# EIB_A79024-001.net
KiCad netlist of a schematic drawn in EAGLE
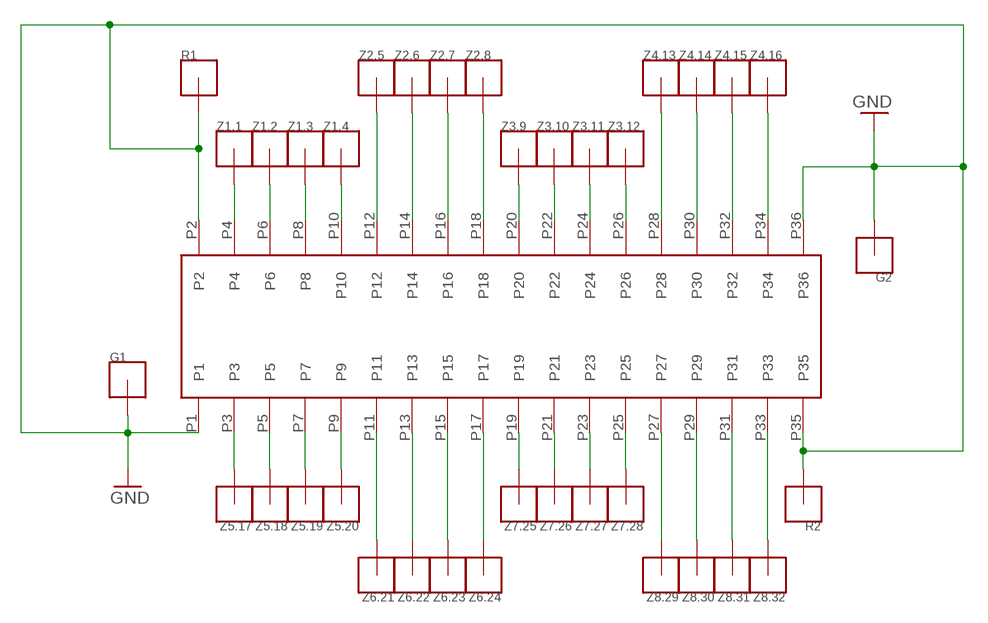
[diagram p0: schematic, sheet 1]

(export (version "E")
  (design (tool "Eeschema 10.0.6"))
  (components
    (comp (ref "A79024")
      (value "OMNETICS")
      (footprint "eagle-import:A79024")
      (libsource (lib "eagle-import") (part "OMNETICS"))
    )
    (comp (ref "G1")
      (value "S_P_HOLE")
      (footprint "eagle-import:S_P_HOLE")
      (libsource (lib "eagle-import") (part "S_P_HOLE"))
    )
    (comp (ref "G2")
      (value "S_P_HOLE")
      (footprint "eagle-import:S_P_HOLE")
      (libsource (lib "eagle-import") (part "S_P_HOLE"))
    )
    (comp (ref "R1")
      (value "S_P_HOLE")
      (footprint "eagle-import:S_P_HOLE")
      (libsource (lib "eagle-import") (part "S_P_HOLE"))
    )
    (comp (ref "R2")
      (value "S_P_HOLE")
      (footprint "eagle-import:S_P_HOLE")
      (libsource (lib "eagle-import") (part "S_P_HOLE"))
    )
    (comp (ref "Z1.1")
      (value "S_P_HOLE")
      (footprint "eagle-import:S_P_HOLE")
      (libsource (lib "eagle-import") (part "S_P_HOLE"))
    )
    (comp (ref "Z1.2")
      (value "S_P_HOLE")
      (footprint "eagle-import:S_P_HOLE")
      (libsource (lib "eagle-import") (part "S_P_HOLE"))
    )
    (comp (ref "Z1.3")
      (value "S_P_HOLE")
      (footprint "eagle-import:S_P_HOLE")
      (libsource (lib "eagle-import") (part "S_P_HOLE"))
    )
    (comp (ref "Z1.4")
      (value "S_P_HOLE")
      (footprint "eagle-import:S_P_HOLE")
      (libsource (lib "eagle-import") (part "S_P_HOLE"))
    )
    (comp (ref "Z2.5")
      (value "S_P_HOLE")
      (footprint "eagle-import:S_P_HOLE")
      (libsource (lib "eagle-import") (part "S_P_HOLE"))
    )
    (comp (ref "Z2.6")
      (value "S_P_HOLE")
      (footprint "eagle-import:S_P_HOLE")
      (libsource (lib "eagle-import") (part "S_P_HOLE"))
    )
    (comp (ref "Z2.7")
      (value "S_P_HOLE")
      (footprint "eagle-import:S_P_HOLE")
      (libsource (lib "eagle-import") (part "S_P_HOLE"))
    )
    (comp (ref "Z2.8")
      (value "S_P_HOLE")
      (footprint "eagle-import:S_P_HOLE")
      (libsource (lib "eagle-import") (part "S_P_HOLE"))
    )
    (comp (ref "Z3.9")
      (value "S_P_HOLE")
      (footprint "eagle-import:S_P_HOLE")
      (libsource (lib "eagle-import") (part "S_P_HOLE"))
    )
    (comp (ref "Z3.10")
      (value "S_P_HOLE")
      (footprint "eagle-import:S_P_HOLE")
      (libsource (lib "eagle-import") (part "S_P_HOLE"))
    )
    (comp (ref "Z3.11")
      (value "S_P_HOLE")
      (footprint "eagle-import:S_P_HOLE")
      (libsource (lib "eagle-import") (part "S_P_HOLE"))
    )
    (comp (ref "Z3.12")
      (value "S_P_HOLE")
      (footprint "eagle-import:S_P_HOLE")
      (libsource (lib "eagle-import") (part "S_P_HOLE"))
    )
    (comp (ref "Z4.13")
      (value "S_P_HOLE")
      (footprint "eagle-import:S_P_HOLE")
      (libsource (lib "eagle-import") (part "S_P_HOLE"))
    )
    (comp (ref "Z4.14")
      (value "S_P_HOLE")
      (footprint "eagle-import:S_P_HOLE")
      (libsource (lib "eagle-import") (part "S_P_HOLE"))
    )
    (comp (ref "Z4.15")
      (value "S_P_HOLE")
      (footprint "eagle-import:S_P_HOLE")
      (libsource (lib "eagle-import") (part "S_P_HOLE"))
    )
    (comp (ref "Z4.16")
      (value "S_P_HOLE")
      (footprint "eagle-import:S_P_HOLE")
      (libsource (lib "eagle-import") (part "S_P_HOLE"))
    )
    (comp (ref "Z5.17")
      (value "S_P_HOLE")
      (footprint "eagle-import:S_P_HOLE")
      (libsource (lib "eagle-import") (part "S_P_HOLE"))
    )
    (comp (ref "Z5.18")
      (value "S_P_HOLE")
      (footprint "eagle-import:S_P_HOLE")
      (libsource (lib "eagle-import") (part "S_P_HOLE"))
    )
    (comp (ref "Z5.19")
      (value "S_P_HOLE")
      (footprint "eagle-import:S_P_HOLE")
      (libsource (lib "eagle-import") (part "S_P_HOLE"))
    )
    (comp (ref "Z5.20")
      (value "S_P_HOLE")
      (footprint "eagle-import:S_P_HOLE")
      (libsource (lib "eagle-import") (part "S_P_HOLE"))
    )
    (comp (ref "Z6.21")
      (value "S_P_HOLE")
      (footprint "eagle-import:S_P_HOLE")
      (libsource (lib "eagle-import") (part "S_P_HOLE"))
    )
    (comp (ref "Z6.22")
      (value "S_P_HOLE")
      (footprint "eagle-import:S_P_HOLE")
      (libsource (lib "eagle-import") (part "S_P_HOLE"))
    )
    (comp (ref "Z6.23")
      (value "S_P_HOLE")
      (footprint "eagle-import:S_P_HOLE")
      (libsource (lib "eagle-import") (part "S_P_HOLE"))
    )
    (comp (ref "Z6.24")
      (value "S_P_HOLE")
      (footprint "eagle-import:S_P_HOLE")
      (libsource (lib "eagle-import") (part "S_P_HOLE"))
    )
    (comp (ref "Z7.25")
      (value "S_P_HOLE")
      (footprint "eagle-import:S_P_HOLE")
      (libsource (lib "eagle-import") (part "S_P_HOLE"))
    )
    (comp (ref "Z7.26")
      (value "S_P_HOLE")
      (footprint "eagle-import:S_P_HOLE")
      (libsource (lib "eagle-import") (part "S_P_HOLE"))
    )
    (comp (ref "Z7.27")
      (value "S_P_HOLE")
      (footprint "eagle-import:S_P_HOLE")
      (libsource (lib "eagle-import") (part "S_P_HOLE"))
    )
    (comp (ref "Z7.28")
      (value "S_P_HOLE")
      (footprint "eagle-import:S_P_HOLE")
      (libsource (lib "eagle-import") (part "S_P_HOLE"))
    )
    (comp (ref "Z8.29")
      (value "S_P_HOLE")
      (footprint "eagle-import:S_P_HOLE")
      (libsource (lib "eagle-import") (part "S_P_HOLE"))
    )
    (comp (ref "Z8.30")
      (value "S_P_HOLE")
      (footprint "eagle-import:S_P_HOLE")
      (libsource (lib "eagle-import") (part "S_P_HOLE"))
    )
    (comp (ref "Z8.31")
      (value "S_P_HOLE")
      (footprint "eagle-import:S_P_HOLE")
      (libsource (lib "eagle-import") (part "S_P_HOLE"))
    )
    (comp (ref "Z8.32")
      (value "S_P_HOLE")
      (footprint "eagle-import:S_P_HOLE")
      (libsource (lib "eagle-import") (part "S_P_HOLE"))
    )
  )
  (nets
    (net (code "1") (name "GND") (class "Default")
      (node (ref "A79024") (pin "P1") (pinfunction "P1_P1") (pintype "bidirectional"))
      (node (ref "A79024") (pin "P2") (pinfunction "P2_P2") (pintype "bidirectional"))
      (node (ref "A79024") (pin "P35") (pinfunction "P35_P35") (pintype "bidirectional"))
      (node (ref "A79024") (pin "P36") (pinfunction "P36_P36") (pintype "bidirectional"))
      (node (ref "G1") (pin "P1") (pinfunction "P1_P1") (pintype "bidirectional"))
      (node (ref "G2") (pin "P1") (pinfunction "P1_P1") (pintype "bidirectional"))
      (node (ref "R1") (pin "P1") (pinfunction "P1_P1") (pintype "bidirectional"))
      (node (ref "R2") (pin "P1") (pinfunction "P1_P1") (pintype "bidirectional"))
    )
    (net (code "2") (name "Net-(A79024-PadP3)") (class "Default")
      (node (ref "A79024") (pin "P3") (pinfunction "P3_P3") (pintype "bidirectional"))
      (node (ref "Z5.17") (pin "P1") (pinfunction "P1_P1") (pintype "bidirectional"))
    )
    (net (code "3") (name "Net-(A79024-PadP4)") (class "Default")
      (node (ref "A79024") (pin "P4") (pinfunction "P4_P4") (pintype "bidirectional"))
      (node (ref "Z1.1") (pin "P1") (pinfunction "P1_P1") (pintype "bidirectional"))
    )
    (net (code "4") (name "Net-(A79024-PadP5)") (class "Default")
      (node (ref "A79024") (pin "P5") (pinfunction "P5_P5") (pintype "bidirectional"))
      (node (ref "Z5.18") (pin "P1") (pinfunction "P1_P1") (pintype "bidirectional"))
    )
    (net (code "5") (name "Net-(A79024-PadP6)") (class "Default")
      (node (ref "A79024") (pin "P6") (pinfunction "P6_P6") (pintype "bidirectional"))
      (node (ref "Z1.2") (pin "P1") (pinfunction "P1_P1") (pintype "bidirectional"))
    )
    (net (code "6") (name "Net-(A79024-PadP7)") (class "Default")
      (node (ref "A79024") (pin "P7") (pinfunction "P7_P7") (pintype "bidirectional"))
      (node (ref "Z5.19") (pin "P1") (pinfunction "P1_P1") (pintype "bidirectional"))
    )
    (net (code "7") (name "Net-(A79024-PadP8)") (class "Default")
      (node (ref "A79024") (pin "P8") (pinfunction "P8_P8") (pintype "bidirectional"))
      (node (ref "Z1.3") (pin "P1") (pinfunction "P1_P1") (pintype "bidirectional"))
    )
    (net (code "8") (name "Net-(A79024-PadP9)") (class "Default")
      (node (ref "A79024") (pin "P9") (pinfunction "P9_P9") (pintype "bidirectional"))
      (node (ref "Z5.20") (pin "P1") (pinfunction "P1_P1") (pintype "bidirectional"))
    )
    (net (code "9") (name "Net-(A79024-PadP10)") (class "Default")
      (node (ref "A79024") (pin "P10") (pinfunction "P10_P10") (pintype "bidirectional"))
      (node (ref "Z1.4") (pin "P1") (pinfunction "P1_P1") (pintype "bidirectional"))
    )
    (net (code "10") (name "Net-(A79024-PadP11)") (class "Default")
      (node (ref "A79024") (pin "P11") (pinfunction "P11_P11") (pintype "bidirectional"))
      (node (ref "Z6.21") (pin "P1") (pinfunction "P1_P1") (pintype "bidirectional"))
    )
    (net (code "11") (name "Net-(A79024-PadP12)") (class "Default")
      (node (ref "A79024") (pin "P12") (pinfunction "P12_P12") (pintype "bidirectional"))
      (node (ref "Z2.5") (pin "P1") (pinfunction "P1_P1") (pintype "bidirectional"))
    )
    (net (code "12") (name "Net-(A79024-PadP13)") (class "Default")
      (node (ref "A79024") (pin "P13") (pinfunction "P13_P13") (pintype "bidirectional"))
      (node (ref "Z6.22") (pin "P1") (pinfunction "P1_P1") (pintype "bidirectional"))
    )
    (net (code "13") (name "Net-(A79024-PadP14)") (class "Default")
      (node (ref "A79024") (pin "P14") (pinfunction "P14_P14") (pintype "bidirectional"))
      (node (ref "Z2.6") (pin "P1") (pinfunction "P1_P1") (pintype "bidirectional"))
    )
    (net (code "14") (name "Net-(A79024-PadP15)") (class "Default")
      (node (ref "A79024") (pin "P15") (pinfunction "P15_P15") (pintype "bidirectional"))
      (node (ref "Z6.23") (pin "P1") (pinfunction "P1_P1") (pintype "bidirectional"))
    )
    (net (code "15") (name "Net-(A79024-PadP16)") (class "Default")
      (node (ref "A79024") (pin "P16") (pinfunction "P16_P16") (pintype "bidirectional"))
      (node (ref "Z2.7") (pin "P1") (pinfunction "P1_P1") (pintype "bidirectional"))
    )
    (net (code "16") (name "Net-(A79024-PadP17)") (class "Default")
      (node (ref "A79024") (pin "P17") (pinfunction "P17_P17") (pintype "bidirectional"))
      (node (ref "Z6.24") (pin "P1") (pinfunction "P1_P1") (pintype "bidirectional"))
    )
    (net (code "17") (name "Net-(A79024-PadP18)") (class "Default")
      (node (ref "A79024") (pin "P18") (pinfunction "P18_P18") (pintype "bidirectional"))
      (node (ref "Z2.8") (pin "P1") (pinfunction "P1_P1") (pintype "bidirectional"))
    )
    (net (code "18") (name "Net-(A79024-PadP19)") (class "Default")
      (node (ref "A79024") (pin "P19") (pinfunction "P19_P19") (pintype "bidirectional"))
      (node (ref "Z7.25") (pin "P1") (pinfunction "P1_P1") (pintype "bidirectional"))
    )
    (net (code "19") (name "Net-(A79024-PadP20)") (class "Default")
      (node (ref "A79024") (pin "P20") (pinfunction "P20_P20") (pintype "bidirectional"))
      (node (ref "Z3.9") (pin "P1") (pinfunction "P1_P1") (pintype "bidirectional"))
    )
    (net (code "20") (name "Net-(A79024-PadP21)") (class "Default")
      (node (ref "A79024") (pin "P21") (pinfunction "P21_P21") (pintype "bidirectional"))
      (node (ref "Z7.26") (pin "P1") (pinfunction "P1_P1") (pintype "bidirectional"))
    )
    (net (code "21") (name "Net-(A79024-PadP22)") (class "Default")
      (node (ref "A79024") (pin "P22") (pinfunction "P22_P22") (pintype "bidirectional"))
      (node (ref "Z3.10") (pin "P1") (pinfunction "P1_P1") (pintype "bidirectional"))
    )
    (net (code "22") (name "Net-(A79024-PadP23)") (class "Default")
      (node (ref "A79024") (pin "P23") (pinfunction "P23_P23") (pintype "bidirectional"))
      (node (ref "Z7.27") (pin "P1") (pinfunction "P1_P1") (pintype "bidirectional"))
    )
    (net (code "23") (name "Net-(A79024-PadP24)") (class "Default")
      (node (ref "A79024") (pin "P24") (pinfunction "P24_P24") (pintype "bidirectional"))
      (node (ref "Z3.11") (pin "P1") (pinfunction "P1_P1") (pintype "bidirectional"))
    )
    (net (code "24") (name "Net-(A79024-PadP25)") (class "Default")
      (node (ref "A79024") (pin "P25") (pinfunction "P25_P25") (pintype "bidirectional"))
      (node (ref "Z7.28") (pin "P1") (pinfunction "P1_P1") (pintype "bidirectional"))
    )
    (net (code "25") (name "Net-(A79024-PadP26)") (class "Default")
      (node (ref "A79024") (pin "P26") (pinfunction "P26_P26") (pintype "bidirectional"))
      (node (ref "Z3.12") (pin "P1") (pinfunction "P1_P1") (pintype "bidirectional"))
    )
    (net (code "26") (name "Net-(A79024-PadP27)") (class "Default")
      (node (ref "A79024") (pin "P27") (pinfunction "P27_P27") (pintype "bidirectional"))
      (node (ref "Z8.29") (pin "P1") (pinfunction "P1_P1") (pintype "bidirectional"))
    )
    (net (code "27") (name "Net-(A79024-PadP28)") (class "Default")
      (node (ref "A79024") (pin "P28") (pinfunction "P28_P28") (pintype "bidirectional"))
      (node (ref "Z4.13") (pin "P1") (pinfunction "P1_P1") (pintype "bidirectional"))
    )
    (net (code "28") (name "Net-(A79024-PadP29)") (class "Default")
      (node (ref "A79024") (pin "P29") (pinfunction "P29_P29") (pintype "bidirectional"))
      (node (ref "Z8.30") (pin "P1") (pinfunction "P1_P1") (pintype "bidirectional"))
    )
    (net (code "29") (name "Net-(A79024-PadP30)") (class "Default")
      (node (ref "A79024") (pin "P30") (pinfunction "P30_P30") (pintype "bidirectional"))
      (node (ref "Z4.14") (pin "P1") (pinfunction "P1_P1") (pintype "bidirectional"))
    )
    (net (code "30") (name "Net-(A79024-PadP31)") (class "Default")
      (node (ref "A79024") (pin "P31") (pinfunction "P31_P31") (pintype "bidirectional"))
      (node (ref "Z8.31") (pin "P1") (pinfunction "P1_P1") (pintype "bidirectional"))
    )
    (net (code "31") (name "Net-(A79024-PadP32)") (class "Default")
      (node (ref "A79024") (pin "P32") (pinfunction "P32_P32") (pintype "bidirectional"))
      (node (ref "Z4.15") (pin "P1") (pinfunction "P1_P1") (pintype "bidirectional"))
    )
    (net (code "32") (name "Net-(A79024-PadP33)") (class "Default")
      (node (ref "A79024") (pin "P33") (pinfunction "P33_P33") (pintype "bidirectional"))
      (node (ref "Z8.32") (pin "P1") (pinfunction "P1_P1") (pintype "bidirectional"))
    )
    (net (code "33") (name "Net-(A79024-PadP34)") (class "Default")
      (node (ref "A79024") (pin "P34") (pinfunction "P34_P34") (pintype "bidirectional"))
      (node (ref "Z4.16") (pin "P1") (pinfunction "P1_P1") (pintype "bidirectional"))
    )
  )
)
